# MCU.net
KiCad netlist of a schematic drawn in Altium Designer
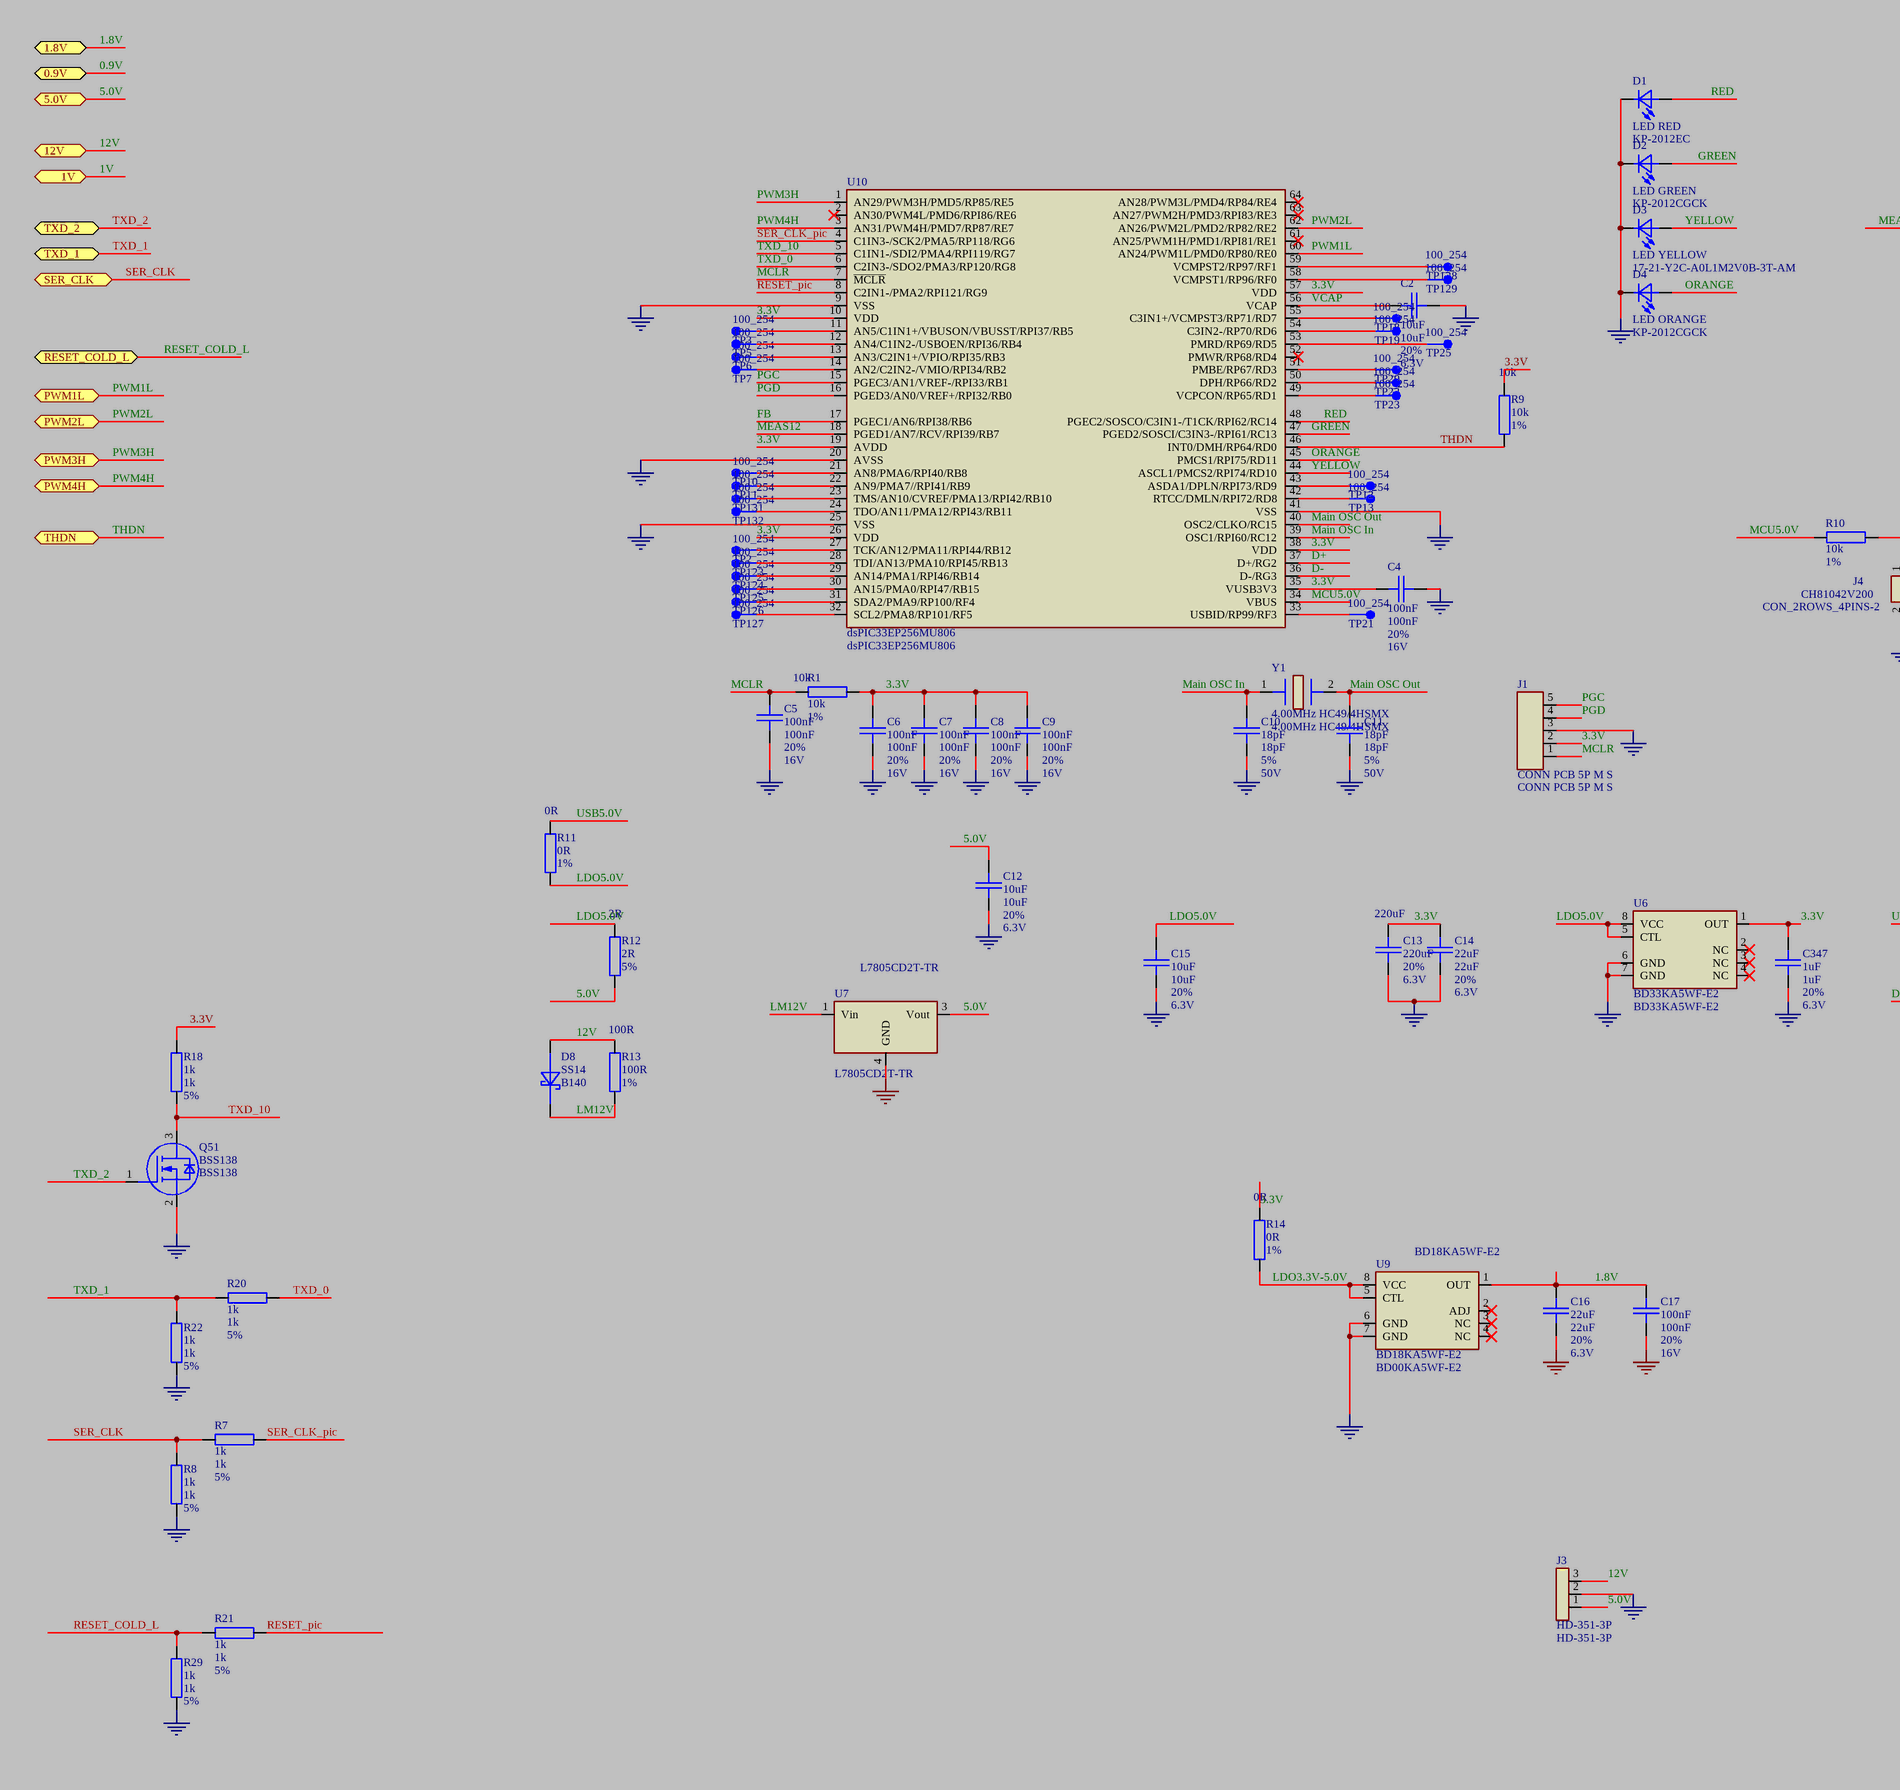
[diagram p0: MCU.SchDoc, left]
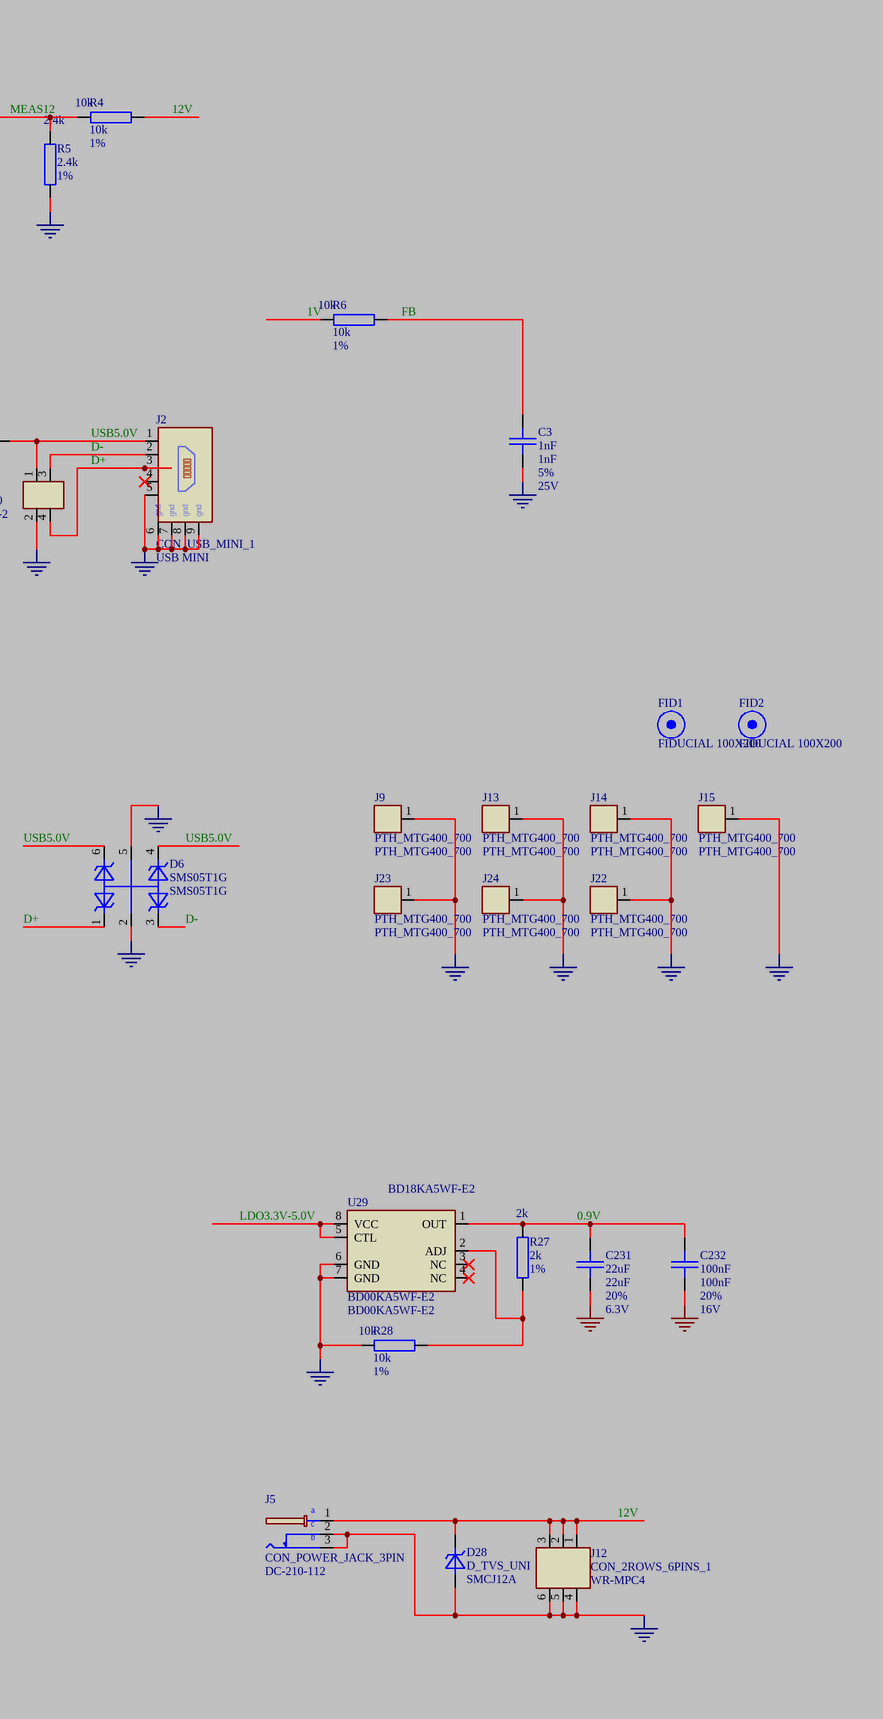
[diagram p1: MCU.SchDoc, right]

(export (version "E")
  (design (tool "Eeschema 10.0.6"))
  (components
    (comp (ref "C2")
      (value "10uF")
      (footprint "SMD_0603_CAPC1608X95N")
      (fields
        (field (name "DB_PART_NUMBER") "CAP000043646")
        (field (name "DB_VALUE") "10uF")
        (field (name "DB_TOLERANCE") "20%")
        (field (name "DB_VOLTAGE") "6.3V")
        (field (name "DB_MANUFACTURER_PART") "KEMET    C0603C106M9PAC")
        (field (name "DB_APPROVED_BY") "ISHIDDEN=T")
      )
      (libsource (lib "Database_Libs1") (part "C"))
    )
    (comp (ref "C3")
      (value "1nF")
      (footprint "SMD_0603_CAPC1608X95N")
      (fields
        (field (name "DB_PART_NUMBER") "CAP000024113")
        (field (name "DB_VALUE") "1nF")
        (field (name "DB_TOLERANCE") "5%")
        (field (name "DB_VOLTAGE") "25V")
        (field (name "DB_MANUFACTURER_PART") "KEMET    C0603C102J3RAC")
        (field (name "DB_APPROVED_BY") "ISHIDDEN=T")
      )
      (libsource (lib "Database_Libs1") (part "C"))
    )
    (comp (ref "C4")
      (value "100nF")
      (footprint "SMD_0402_CAPC1005X55N")
      (fields
        (field (name "DB_PART_NUMBER") "CAP000022751")
        (field (name "DB_VALUE") "100nF")
        (field (name "DB_TOLERANCE") "20%")
        (field (name "DB_VOLTAGE") "16V")
        (field (name "DB_MANUFACTURER_PART") "KEMET    C0402F104M4RAC")
        (field (name "DB_APPROVED_BY") "ISHIDDEN=T")
      )
      (libsource (lib "Database_Libs1") (part "C"))
    )
    (comp (ref "C5")
      (value "100nF")
      (footprint "SMD_0402_CAPC1005X55N")
      (fields
        (field (name "DB_PART_NUMBER") "CAP000022751")
        (field (name "DB_VALUE") "100nF")
        (field (name "DB_TOLERANCE") "20%")
        (field (name "DB_VOLTAGE") "16V")
        (field (name "DB_MANUFACTURER_PART") "KEMET    C0402F104M4RAC")
        (field (name "DB_APPROVED_BY") "ISHIDDEN=T")
      )
      (libsource (lib "Database_Libs1") (part "C"))
    )
    (comp (ref "C6")
      (value "100nF")
      (footprint "SMD_0402_CAPC1005X55N")
      (fields
        (field (name "DB_PART_NUMBER") "CAP000022751")
        (field (name "DB_VALUE") "100nF")
        (field (name "DB_TOLERANCE") "20%")
        (field (name "DB_VOLTAGE") "16V")
        (field (name "DB_MANUFACTURER_PART") "KEMET    C0402F104M4RAC")
        (field (name "DB_APPROVED_BY") "ISHIDDEN=T")
      )
      (libsource (lib "Database_Libs1") (part "C"))
    )
    (comp (ref "C7")
      (value "100nF")
      (footprint "SMD_0402_CAPC1005X55N")
      (fields
        (field (name "DB_PART_NUMBER") "CAP000022751")
        (field (name "DB_VALUE") "100nF")
        (field (name "DB_TOLERANCE") "20%")
        (field (name "DB_VOLTAGE") "16V")
        (field (name "DB_MANUFACTURER_PART") "KEMET    C0402F104M4RAC")
        (field (name "DB_APPROVED_BY") "ISHIDDEN=T")
      )
      (libsource (lib "Database_Libs1") (part "C"))
    )
    (comp (ref "C8")
      (value "100nF")
      (footprint "SMD_0402_CAPC1005X55N")
      (fields
        (field (name "DB_PART_NUMBER") "CAP000022751")
        (field (name "DB_VALUE") "100nF")
        (field (name "DB_TOLERANCE") "20%")
        (field (name "DB_VOLTAGE") "16V")
        (field (name "DB_MANUFACTURER_PART") "KEMET    C0402F104M4RAC")
        (field (name "DB_APPROVED_BY") "ISHIDDEN=T")
      )
      (libsource (lib "Database_Libs1") (part "C"))
    )
    (comp (ref "C9")
      (value "100nF")
      (footprint "SMD_0402_CAPC1005X55N")
      (fields
        (field (name "DB_PART_NUMBER") "CAP000022751")
        (field (name "DB_VALUE") "100nF")
        (field (name "DB_TOLERANCE") "20%")
        (field (name "DB_VOLTAGE") "16V")
        (field (name "DB_MANUFACTURER_PART") "KEMET    C0402F104M4RAC")
        (field (name "DB_APPROVED_BY") "ISHIDDEN=T")
      )
      (libsource (lib "Database_Libs1") (part "C"))
    )
    (comp (ref "C10")
      (value "18pF")
      (footprint "SMD_0603_CAPC1608X95N")
      (fields
        (field (name "DB_PART_NUMBER") "CAP000031922")
        (field (name "DB_VALUE") "18pF")
        (field (name "DB_TOLERANCE") "5%")
        (field (name "DB_VOLTAGE") "50V")
        (field (name "DB_MANUFACTURER_PART") "KEMET    C0603C180J5GAC")
        (field (name "DB_APPROVED_BY") "ISHIDDEN=T")
      )
      (libsource (lib "Database_Libs1") (part "C"))
    )
    (comp (ref "C11")
      (value "18pF")
      (footprint "SMD_0603_CAPC1608X95N")
      (fields
        (field (name "DB_PART_NUMBER") "CAP000031922")
        (field (name "DB_VALUE") "18pF")
        (field (name "DB_TOLERANCE") "5%")
        (field (name "DB_VOLTAGE") "50V")
        (field (name "DB_MANUFACTURER_PART") "KEMET    C0603C180J5GAC")
        (field (name "DB_APPROVED_BY") "ISHIDDEN=T")
      )
      (libsource (lib "Database_Libs1") (part "C"))
    )
    (comp (ref "C12")
      (value "10uF")
      (footprint "SMD_0603_CAPC1608X95N")
      (fields
        (field (name "DB_PART_NUMBER") "CAP000043646")
        (field (name "DB_VALUE") "10uF")
        (field (name "DB_TOLERANCE") "20%")
        (field (name "DB_VOLTAGE") "6.3V")
        (field (name "DB_MANUFACTURER_PART") "KEMET    C0603C106M9PAC")
        (field (name "DB_APPROVED_BY") "ISHIDDEN=T")
      )
      (libsource (lib "Database_Libs1") (part "C"))
    )
    (comp (ref "C13")
      (value "220uF")
      (footprint "SMD_1210_CAPC3225X279N")
      (fields
        (field (name "DB_PART_NUMBER") "CAP000047355")
        (field (name "DB_VALUE") "220uF")
        (field (name "DB_TOLERANCE") "20%")
        (field (name "DB_VOLTAGE") "6.3V")
        (field (name "DB_MANUFACTURER_PART") "SAMSUNG    CL32A227MQVNNNE")
        (field (name "DB_APPROVED_BY") "VSN")
      )
      (libsource (lib "Database_Libs1") (part "C"))
    )
    (comp (ref "C14")
      (value "22uF")
      (footprint "SMD_0805_CAPC2012X145N")
      (fields
        (field (name "DB_PART_NUMBER") "CAP000043686")
        (field (name "DB_VALUE") "22uF")
        (field (name "DB_TOLERANCE") "20%")
        (field (name "DB_VOLTAGE") "6.3V")
        (field (name "DB_MANUFACTURER_PART") "KEMET    C0805C226M9PAC")
        (field (name "DB_APPROVED_BY") "ISHIDDEN=T")
      )
      (libsource (lib "Database_Libs1") (part "C"))
    )
    (comp (ref "C15")
      (value "10uF")
      (footprint "SMD_0603_CAPC1608X95N")
      (fields
        (field (name "DB_PART_NUMBER") "CAP000043646")
        (field (name "DB_VALUE") "10uF")
        (field (name "DB_TOLERANCE") "20%")
        (field (name "DB_VOLTAGE") "6.3V")
        (field (name "DB_MANUFACTURER_PART") "KEMET    C0603C106M9PAC")
        (field (name "DB_APPROVED_BY") "ISHIDDEN=T")
      )
      (libsource (lib "Database_Libs1") (part "C"))
    )
    (comp (ref "C16")
      (value "22uF")
      (footprint "SMD_0805_CAPC2012X145N")
      (fields
        (field (name "DB_PART_NUMBER") "CAP000043686")
        (field (name "DB_VALUE") "22uF")
        (field (name "DB_TOLERANCE") "20%")
        (field (name "DB_VOLTAGE") "6.3V")
        (field (name "DB_MANUFACTURER_PART") "KEMET    C0805C226M9PAC")
        (field (name "DB_APPROVED_BY") "ISHIDDEN=T")
      )
      (libsource (lib "Database_Libs1") (part "C"))
    )
    (comp (ref "C17")
      (value "100nF")
      (footprint "SMD_0402_CAPC1005X55N")
      (fields
        (field (name "DB_PART_NUMBER") "CAP000022751")
        (field (name "DB_VALUE") "100nF")
        (field (name "DB_TOLERANCE") "20%")
        (field (name "DB_VOLTAGE") "16V")
        (field (name "DB_MANUFACTURER_PART") "KEMET    C0402F104M4RAC")
        (field (name "DB_APPROVED_BY") "ISHIDDEN=T")
      )
      (libsource (lib "Database_Libs1") (part "C"))
    )
    (comp (ref "C231")
      (value "22uF")
      (footprint "SMD_0805_CAPC2012X145N")
      (fields
        (field (name "DB_PART_NUMBER") "CAP000043686")
        (field (name "DB_VALUE") "22uF")
        (field (name "DB_TOLERANCE") "20%")
        (field (name "DB_VOLTAGE") "6.3V")
        (field (name "DB_MANUFACTURER_PART") "KEMET    C0805C226M9PAC")
        (field (name "DB_APPROVED_BY") "ISHIDDEN=T")
      )
      (libsource (lib "Database_Libs1") (part "C"))
    )
    (comp (ref "C232")
      (value "100nF")
      (footprint "SMD_0402_CAPC1005X55N")
      (fields
        (field (name "DB_PART_NUMBER") "CAP000022751")
        (field (name "DB_VALUE") "100nF")
        (field (name "DB_TOLERANCE") "20%")
        (field (name "DB_VOLTAGE") "16V")
        (field (name "DB_MANUFACTURER_PART") "KEMET    C0402F104M4RAC")
        (field (name "DB_APPROVED_BY") "ISHIDDEN=T")
      )
      (libsource (lib "Database_Libs1") (part "C"))
    )
    (comp (ref "C347")
      (value "1uF")
      (footprint "SMD_0603_CAPC1608X95N")
      (fields
        (field (name "DB_PART_NUMBER") "CAP000043344")
        (field (name "DB_VALUE") "1uF")
        (field (name "DB_TOLERANCE") "20%")
        (field (name "DB_VOLTAGE") "6.3V")
        (field (name "DB_MANUFACTURER_PART") "KEMET    C0603C105M9PAC")
        (field (name "DB_APPROVED_BY") "ISHIDDEN=T")
      )
      (libsource (lib "Database_Libs1") (part "C"))
    )
    (comp (ref "D1")
      (value "LED RED")
      (footprint "SMD_0805_LED2012X100N")
      (fields
        (field (name "DB_PART_NUMBER") "OPT000000095")
        (field (name "DB_VALUE") "KP-2012EC")
        (field (name "DB_MANUFACTURER_PART") "KINGBRIGHT       KP-2012EC")
        (field (name "DB_APPROVED_BY") "VSN")
      )
      (libsource (lib "Database_Libs1") (part "LED"))
    )
    (comp (ref "D2")
      (value "LED GREEN")
      (footprint "SMD_0805_LED2012X100N")
      (fields
        (field (name "DB_PART_NUMBER") "OPT000000096")
        (field (name "DB_VALUE") "KP-2012CGCK")
        (field (name "DB_MANUFACTURER_PART") "KINGBRIGHT       KP-2012CGCK")
        (field (name "DB_APPROVED_BY") "VSN")
      )
      (libsource (lib "Database_Libs1") (part "LED"))
    )
    (comp (ref "D3")
      (value "LED YELLOW")
      (footprint "SMD_0805_LED2012X100N")
      (fields
        (field (name "DB_PART_NUMBER") "OPT000000092")
        (field (name "DB_VALUE") "17-21-Y2C-A0L1M2V0B-3T-AM")
        (field (name "DB_MANUFACTURER_PART") "EVERLIGHT       17-21-Y2C-A0L1M2V0B-3T-AM")
        (field (name "DB_APPROVED_BY") "VSN")
      )
      (libsource (lib "Database_Libs1") (part "LED"))
    )
    (comp (ref "D4")
      (value "LED ORANGE")
      (footprint "SMD_0805_LED2012X100N")
      (fields
        (field (name "DB_PART_NUMBER") "OPT0000000zz")
        (field (name "DB_VALUE") "KP-2012CGCK")
        (field (name "DB_MANUFACTURER_PART") "KINGBRIGHT       KP-2012CGCK")
        (field (name "DB_APPROVED_BY") "VSN")
      )
      (libsource (lib "Database_Libs1") (part "LED"))
    )
    (comp (ref "D6")
      (value "SMS05T1G")
      (footprint "SMD_SOT457_SOT95P275X110-6N")
      (fields
        (field (name "DB_PART_NUMBER") "DDE000002846")
        (field (name "DB_VALUE") "SMS05T1G")
        (field (name "DB_MANUFACTURER_PART") "ON SEMICONDUCTOR        SMS05T1G")
        (field (name "DB_APPROVED_BY") "VSN")
      )
      (libsource (lib "Database_Libs1") (part "D_TVS_QUAD_C1A2C3C4A5C6"))
    )
    (comp (ref "D8")
      (value "SS14")
      (footprint "SMD_DO214AC_SMA")
      (fields
        (field (name "DB_PART_NUMBER") "DDE000000580")
        (field (name "DB_VALUE") "B140")
        (field (name "DB_MANUFACTURER_PART") "Diodes        B140")
        (field (name "DB_APPROVED_BY") "ISHIDDEN=T")
      )
      (libsource (lib "Database_Libs1") (part "D_STKY"))
    )
    (comp (ref "D28")
      (value "D_TVS_UNI")
      (footprint "SMD_DO214AC_SMC")
      (fields
        (field (name "DB_PART_NUMBER") "DDE000001725")
        (field (name "DB_VALUE") "SMCJ12A")
        (field (name "DB_MANUFACTURER_PART") "Diodes        SMCJ12A")
        (field (name "DB_APPROVED_BY") "ISHIDDEN=T")
      )
      (libsource (lib "Database_Libs1") (part "D_TVS_UNI"))
    )
    (comp (ref "FID1")
      (value "FIDUCIAL 100X200")
      (footprint "FID100X200")
      (fields
        (field (name "DB_PART_NUMBER") "FID000000001")
        (field (name "DB_MANUFACTURER_PART") "ISHIDDEN=T")
        (field (name "DB_APPROVED_BY") "ISHIDDEN=T")
      )
      (libsource (lib "Database_Libs1") (part "FIDUCIAL"))
    )
    (comp (ref "FID2")
      (value "FIDUCIAL 100X200")
      (footprint "FID100X200")
      (fields
        (field (name "DB_PART_NUMBER") "FID000000001")
        (field (name "DB_MANUFACTURER_PART") "ISHIDDEN=T")
        (field (name "DB_APPROVED_BY") "ISHIDDEN=T")
      )
      (libsource (lib "Database_Libs1") (part "FIDUCIAL"))
    )
    (comp (ref "J1")
      (value "CONN PCB 5P M S")
      (footprint "PTH_HDRV05W64P254_1X05")
      (fields
        (field (name "DB_PART_NUMBER") "CON000000006")
        (field (name "DB_VALUE") "CONN PCB 5P M S")
        (field (name "DB_MANUFACTURER_PART") "W+P        143-12-005-00")
        (field (name "DB_APPROVED_BY") "VSN")
      )
      (libsource (lib "Database_Libs1") (part "CON_5PINS"))
    )
    (comp (ref "J2")
      (value "CON_USB_MINI_1")
      (footprint "SMD_CON-CVILUX-CU04-SCM15B0")
      (fields
        (field (name "DB_PART_NUMBER") "CON000000048")
        (field (name "DB_VALUE") "USB MINI")
        (field (name "DB_MANUFACTURER_PART") "CVILUX       CU04-SCM15B0-R0-LF")
        (field (name "DB_APPROVED_BY") "VSN")
      )
      (libsource (lib "Database_Libs1") (part "CON_USB_MINI_1"))
    )
    (comp (ref "J3")
      (value "HD-351-3P")
      (footprint "PTH_CON_HD-351-3P")
      (fields
        (field (name "DB_PART_NUMBER") "CON000000272")
        (field (name "DB_VALUE") "HD-351-3P")
        (field (name "DB_MANUFACTURER_PART") "HOW DER      HD-351-3P")
        (field (name "DB_APPROVED_BY") "VSN")
      )
      (libsource (lib "Database_Libs1") (part "CON_3PINS"))
    )
    (comp (ref "J4")
      (value "CON_2ROWS_4PINS-2")
      (footprint "PTH_HDRV40W6240P254_2X02_M")
      (fields
        (field (name "DB_PART_NUMBER") "CON000000298")
        (field (name "DB_VALUE") "CH81042V200")
        (field (name "DB_MANUFACTURER_PART") "CVILUX        CH81042V200")
        (field (name "DB_APPROVED_BY") "VSN")
      )
      (libsource (lib "Database_Libs1") (part "CON_2ROWS_4PINS-2"))
    )
    (comp (ref "J5")
      (value "CON_POWER_JACK_3PIN")
      (footprint "PTH_DC-POWER-JACK_210-112")
      (fields
        (field (name "DB_PART_NUMBER") "CON000000026")
        (field (name "DB_VALUE") "DC-210-112")
        (field (name "DB_MANUFACTURER_PART") "HONBO       DC-210-112")
        (field (name "DB_APPROVED_BY") "VSN")
      )
      (libsource (lib "Database_Libs1") (part "CON_POWER_JACK_3PIN"))
    )
    (comp (ref "J9")
      (value "PTH_MTG400_700")
      (footprint "PTH_MTG400_700")
      (fields
        (field (name "DB_PART_NUMBER") "MTH000000030")
        (field (name "DB_VALUE") "PTH_MTG400_700")
        (field (name "DB_APPROVED_BY") "VSN")
      )
      (libsource (lib "Database_Libs1") (part "CON_1PIN"))
    )
    (comp (ref "J12")
      (value "CON_2ROWS_6PINS_1")
      (footprint "PTH_CON_WR-MRC4-6P_S")
      (fields
        (field (name "DB_PART_NUMBER") "CON000000279")
        (field (name "DB_VALUE") "WR-MPC4")
        (field (name "DB_MANUFACTURER_PART") "WE        	649 006 211 22")
        (field (name "DB_APPROVED_BY") "VSN")
      )
      (libsource (lib "Database_Libs1") (part "CON_2ROWS_6PINS_1"))
    )
    (comp (ref "J13")
      (value "PTH_MTG400_700")
      (footprint "PTH_MTG400_700")
      (fields
        (field (name "DB_PART_NUMBER") "MTH000000030")
        (field (name "DB_VALUE") "PTH_MTG400_700")
        (field (name "DB_APPROVED_BY") "VSN")
      )
      (libsource (lib "Database_Libs1") (part "CON_1PIN"))
    )
    (comp (ref "J14")
      (value "PTH_MTG400_700")
      (footprint "PTH_MTG400_700")
      (fields
        (field (name "DB_PART_NUMBER") "MTH000000030")
        (field (name "DB_VALUE") "PTH_MTG400_700")
        (field (name "DB_APPROVED_BY") "VSN")
      )
      (libsource (lib "Database_Libs1") (part "CON_1PIN"))
    )
    (comp (ref "J15")
      (value "PTH_MTG400_700")
      (footprint "PTH_MTG400_700")
      (fields
        (field (name "DB_PART_NUMBER") "MTH000000030")
        (field (name "DB_VALUE") "PTH_MTG400_700")
        (field (name "DB_APPROVED_BY") "VSN")
      )
      (libsource (lib "Database_Libs1") (part "CON_1PIN"))
    )
    (comp (ref "J22")
      (value "PTH_MTG400_700")
      (footprint "PTH_MTG400_700")
      (fields
        (field (name "DB_PART_NUMBER") "MTH000000030")
        (field (name "DB_VALUE") "PTH_MTG400_700")
        (field (name "DB_APPROVED_BY") "VSN")
      )
      (libsource (lib "Database_Libs1") (part "CON_1PIN"))
    )
    (comp (ref "J23")
      (value "PTH_MTG400_700")
      (footprint "PTH_MTG400_700")
      (fields
        (field (name "DB_PART_NUMBER") "MTH000000030")
        (field (name "DB_VALUE") "PTH_MTG400_700")
        (field (name "DB_APPROVED_BY") "VSN")
      )
      (libsource (lib "Database_Libs1") (part "CON_1PIN"))
    )
    (comp (ref "J24")
      (value "PTH_MTG400_700")
      (footprint "PTH_MTG400_700")
      (fields
        (field (name "DB_PART_NUMBER") "MTH000000030")
        (field (name "DB_VALUE") "PTH_MTG400_700")
        (field (name "DB_APPROVED_BY") "VSN")
      )
      (libsource (lib "Database_Libs1") (part "CON_1PIN"))
    )
    (comp (ref "Q51")
      (value "BSS138")
      (footprint "SMD_SOT23_SOT95P240X112-3N")
      (fields
        (field (name "DB_PART_NUMBER") "TRA000001460")
        (field (name "DB_VALUE") "BSS138")
        (field (name "DB_MANUFACTURER_PART") "FAIRCHILD        BSS138LT1G")
        (field (name "DB_APPROVED_BY") "VSN")
      )
      (libsource (lib "Database_Libs1") (part "MOS_N_D1_G1S2D3"))
    )
    (comp (ref "R1")
      (value "10k")
      (footprint "SMD_0603_RESC1608X55N")
      (fields
        (field (name "DB_PART_NUMBER") "RES000008663")
        (field (name "DB_VALUE") "10k")
        (field (name "DB_TOLERANCE") "1%")
        (field (name "DB_MANUFACTURER_PART") "YAGEO    RC0603FR-0710KL")
        (field (name "DB_APPROVED_BY") "VSN")
      )
      (libsource (lib "Database_Libs1") (part "R"))
    )
    (comp (ref "R4")
      (value "10k")
      (footprint "SMD_0603_RESC1608X55N")
      (fields
        (field (name "DB_PART_NUMBER") "RES000008663")
        (field (name "DB_VALUE") "10k")
        (field (name "DB_TOLERANCE") "1%")
        (field (name "DB_MANUFACTURER_PART") "YAGEO    RC0603FR-0710KL")
        (field (name "DB_APPROVED_BY") "VSN")
      )
      (libsource (lib "Database_Libs1") (part "R"))
    )
    (comp (ref "R5")
      (value "2.4k")
      (footprint "SMD_0603_RESC1608X55N")
      (fields
        (field (name "DB_PART_NUMBER") "RES000006261")
        (field (name "DB_VALUE") "2.4k")
        (field (name "DB_TOLERANCE") "1%")
        (field (name "DB_MANUFACTURER_PART") "YAGEO    RC0603FR-072K4")
        (field (name "DB_APPROVED_BY") "ISHIDDEN=T")
      )
      (libsource (lib "Database_Libs1") (part "R"))
    )
    (comp (ref "R6")
      (value "10k")
      (footprint "SMD_0603_RESC1608X55N")
      (fields
        (field (name "DB_PART_NUMBER") "RES000008663")
        (field (name "DB_VALUE") "10k")
        (field (name "DB_TOLERANCE") "1%")
        (field (name "DB_MANUFACTURER_PART") "YAGEO    RC0603FR-0710KL")
        (field (name "DB_APPROVED_BY") "VSN")
      )
      (libsource (lib "Database_Libs1") (part "R"))
    )
    (comp (ref "R7")
      (value "1k")
      (footprint "SMD_0603_RESC1608X55N")
      (fields
        (field (name "DB_PART_NUMBER") "RES000008858")
        (field (name "DB_VALUE") "1k")
        (field (name "DB_TOLERANCE") "5%")
        (field (name "DB_MANUFACTURER_PART") "YAGEO    AC0603JR-071KL")
        (field (name "DB_APPROVED_BY") "VSN")
      )
      (libsource (lib "Database_Libs1") (part "R"))
    )
    (comp (ref "R8")
      (value "1k")
      (footprint "SMD_0603_RESC1608X55N")
      (fields
        (field (name "DB_PART_NUMBER") "RES000008858")
        (field (name "DB_VALUE") "1k")
        (field (name "DB_TOLERANCE") "5%")
        (field (name "DB_MANUFACTURER_PART") "YAGEO    AC0603JR-071KL")
        (field (name "DB_APPROVED_BY") "VSN")
      )
      (libsource (lib "Database_Libs1") (part "R"))
    )
    (comp (ref "R9")
      (value "10k")
      (footprint "SMD_0603_RESC1608X55N")
      (fields
        (field (name "DB_PART_NUMBER") "RES000008663")
        (field (name "DB_VALUE") "10k")
        (field (name "DB_TOLERANCE") "1%")
        (field (name "DB_MANUFACTURER_PART") "YAGEO    RC0603FR-0710KL")
        (field (name "DB_APPROVED_BY") "VSN")
      )
      (libsource (lib "Database_Libs1") (part "R"))
    )
    (comp (ref "R10")
      (value "R")
      (footprint "SMD_0603_RESC1608X55N")
      (fields
        (field (name "DB_PART_NUMBER") "RES000008663")
        (field (name "DB_VALUE") "10k")
        (field (name "DB_TOLERANCE") "1%")
        (field (name "DB_MANUFACTURER_PART") "YAGEO    RC0603FR-0710KL")
        (field (name "DB_APPROVED_BY") "VSN")
      )
      (libsource (lib "Database_Libs1") (part "R"))
    )
    (comp (ref "R11")
      (value "0R")
      (footprint "SMD_0603_RESC1608X55N")
      (fields
        (field (name "DB_PART_NUMBER") "RES000008926")
        (field (name "DB_VALUE") "0R")
        (field (name "DB_TOLERANCE") "1%")
        (field (name "DB_MANUFACTURER_PART") "YAGEO    AC0603FR-070RL")
        (field (name "DB_APPROVED_BY") "VSN")
      )
      (libsource (lib "Database_Libs1") (part "R"))
    )
    (comp (ref "R12")
      (value "2R")
      (footprint "SMD_1206_RESC3216X65N")
      (fields
        (field (name "DB_PART_NUMBER") "RES000007051")
        (field (name "DB_VALUE") "2R")
        (field (name "DB_TOLERANCE") "5%")
        (field (name "DB_MANUFACTURER_PART") "YAGEO    RC1206JR-072R")
        (field (name "DB_APPROVED_BY") "ISHIDDEN=T")
      )
      (libsource (lib "Database_Libs1") (part "R"))
    )
    (comp (ref "R13")
      (value "100R")
      (footprint "SMD_1206_RESC3216X65N")
      (fields
        (field (name "DB_PART_NUMBER") "RES000006922")
        (field (name "DB_VALUE") "100R")
        (field (name "DB_TOLERANCE") "1%")
        (field (name "DB_MANUFACTURER_PART") "YAGEO    RC1206FR-07100R")
        (field (name "DB_APPROVED_BY") "ISHIDDEN=T")
      )
      (libsource (lib "Database_Libs1") (part "R"))
    )
    (comp (ref "R14")
      (value "0R")
      (footprint "SMD_1206_RESC3216X65N")
      (fields
        (field (name "DB_PART_NUMBER") "RES000008756")
        (field (name "DB_VALUE") "0R")
        (field (name "DB_TOLERANCE") "1%")
        (field (name "DB_MANUFACTURER_PART") "YAGEO    AC1206FR-070RL")
        (field (name "DB_APPROVED_BY") "VSN")
      )
      (libsource (lib "Database_Libs1") (part "R"))
    )
    (comp (ref "R18")
      (value "1k")
      (footprint "SMD_0603_RESC1608X55N")
      (fields
        (field (name "DB_PART_NUMBER") "RES000008858")
        (field (name "DB_VALUE") "1k")
        (field (name "DB_TOLERANCE") "5%")
        (field (name "DB_MANUFACTURER_PART") "YAGEO    AC0603JR-071KL")
        (field (name "DB_APPROVED_BY") "VSN")
      )
      (libsource (lib "Database_Libs1") (part "R"))
    )
    (comp (ref "R20")
      (value "1k")
      (footprint "SMD_0603_RESC1608X55N")
      (fields
        (field (name "DB_PART_NUMBER") "RES000008858")
        (field (name "DB_VALUE") "1k")
        (field (name "DB_TOLERANCE") "5%")
        (field (name "DB_MANUFACTURER_PART") "YAGEO    AC0603JR-071KL")
        (field (name "DB_APPROVED_BY") "VSN")
      )
      (libsource (lib "Database_Libs1") (part "R"))
    )
    (comp (ref "R21")
      (value "1k")
      (footprint "SMD_0603_RESC1608X55N")
      (fields
        (field (name "DB_PART_NUMBER") "RES000008858")
        (field (name "DB_VALUE") "1k")
        (field (name "DB_TOLERANCE") "5%")
        (field (name "DB_MANUFACTURER_PART") "YAGEO    AC0603JR-071KL")
        (field (name "DB_APPROVED_BY") "VSN")
      )
      (libsource (lib "Database_Libs1") (part "R"))
    )
    (comp (ref "R22")
      (value "1k")
      (footprint "SMD_0603_RESC1608X55N")
      (fields
        (field (name "DB_PART_NUMBER") "RES000008858")
        (field (name "DB_VALUE") "1k")
        (field (name "DB_TOLERANCE") "5%")
        (field (name "DB_MANUFACTURER_PART") "YAGEO    AC0603JR-071KL")
        (field (name "DB_APPROVED_BY") "VSN")
      )
      (libsource (lib "Database_Libs1") (part "R"))
    )
    (comp (ref "R27")
      (value "2k")
      (footprint "SMD_0603_RESC1608X55N")
      (fields
        (field (name "DB_PART_NUMBER") "RES000006259")
        (field (name "DB_VALUE") "2k")
        (field (name "DB_TOLERANCE") "1%")
        (field (name "DB_MANUFACTURER_PART") "YAGEO    RC0603FR-072K")
        (field (name "DB_APPROVED_BY") "ISHIDDEN=T")
      )
      (libsource (lib "Database_Libs1") (part "R"))
    )
    (comp (ref "R28")
      (value "10k")
      (footprint "SMD_0603_RESC1608X55N")
      (fields
        (field (name "DB_PART_NUMBER") "RES000006276")
        (field (name "DB_VALUE") "10k")
        (field (name "DB_TOLERANCE") "1%")
        (field (name "DB_MANUFACTURER_PART") "YAGEO    RC0603FR-0710K")
        (field (name "DB_APPROVED_BY") "ISHIDDEN=T")
      )
      (libsource (lib "Database_Libs1") (part "R"))
    )
    (comp (ref "R29")
      (value "1k")
      (footprint "SMD_0603_RESC1608X55N")
      (fields
        (field (name "DB_PART_NUMBER") "RES000008858")
        (field (name "DB_VALUE") "1k")
        (field (name "DB_TOLERANCE") "5%")
        (field (name "DB_MANUFACTURER_PART") "YAGEO    AC0603JR-071KL")
        (field (name "DB_APPROVED_BY") "VSN")
      )
      (libsource (lib "Database_Libs1") (part "R"))
    )
    (comp (ref "TP2")
      (value "100_254")
      (footprint "SMD_TP_100-254")
      (fields
        (field (name "DB_PART_NUMBER") "TPO000000001")
        (field (name "DB_MANUFACTURER_PART") "ISHIDDEN=T")
        (field (name "DB_APPROVED_BY") "ISHIDDEN=T")
      )
      (libsource (lib "Database_Libs1") (part "TEST_POINT_1"))
    )
    (comp (ref "TP3")
      (value "100_254")
      (footprint "SMD_TP_100-254")
      (fields
        (field (name "DB_PART_NUMBER") "TPO000000001")
        (field (name "DB_MANUFACTURER_PART") "ISHIDDEN=T")
        (field (name "DB_APPROVED_BY") "ISHIDDEN=T")
      )
      (libsource (lib "Database_Libs1") (part "TEST_POINT_1"))
    )
    (comp (ref "TP5")
      (value "100_254")
      (footprint "SMD_TP_100-254")
      (fields
        (field (name "DB_PART_NUMBER") "TPO000000001")
        (field (name "DB_MANUFACTURER_PART") "ISHIDDEN=T")
        (field (name "DB_APPROVED_BY") "ISHIDDEN=T")
      )
      (libsource (lib "Database_Libs1") (part "TEST_POINT_1"))
    )
    (comp (ref "TP6")
      (value "100_254")
      (footprint "SMD_TP_100-254")
      (fields
        (field (name "DB_PART_NUMBER") "TPO000000001")
        (field (name "DB_MANUFACTURER_PART") "ISHIDDEN=T")
        (field (name "DB_APPROVED_BY") "ISHIDDEN=T")
      )
      (libsource (lib "Database_Libs1") (part "TEST_POINT_1"))
    )
    (comp (ref "TP7")
      (value "100_254")
      (footprint "SMD_TP_100-254")
      (fields
        (field (name "DB_PART_NUMBER") "TPO000000001")
        (field (name "DB_MANUFACTURER_PART") "ISHIDDEN=T")
        (field (name "DB_APPROVED_BY") "ISHIDDEN=T")
      )
      (libsource (lib "Database_Libs1") (part "TEST_POINT_1"))
    )
    (comp (ref "TP10")
      (value "100_254")
      (footprint "SMD_TP_100-254")
      (fields
        (field (name "DB_PART_NUMBER") "TPO000000001")
        (field (name "DB_MANUFACTURER_PART") "ISHIDDEN=T")
        (field (name "DB_APPROVED_BY") "ISHIDDEN=T")
      )
      (libsource (lib "Database_Libs1") (part "TEST_POINT_1"))
    )
    (comp (ref "TP11")
      (value "100_254")
      (footprint "SMD_TP_100-254")
      (fields
        (field (name "DB_PART_NUMBER") "TPO000000001")
        (field (name "DB_MANUFACTURER_PART") "ISHIDDEN=T")
        (field (name "DB_APPROVED_BY") "ISHIDDEN=T")
      )
      (libsource (lib "Database_Libs1") (part "TEST_POINT_1"))
    )
    (comp (ref "TP12")
      (value "100_254")
      (footprint "SMD_TP_100-254")
      (fields
        (field (name "DB_PART_NUMBER") "TPO000000001")
        (field (name "DB_MANUFACTURER_PART") "ISHIDDEN=T")
        (field (name "DB_APPROVED_BY") "ISHIDDEN=T")
      )
      (libsource (lib "Database_Libs1") (part "TEST_POINT_1"))
    )
    (comp (ref "TP13")
      (value "100_254")
      (footprint "SMD_TP_100-254")
      (fields
        (field (name "DB_PART_NUMBER") "TPO000000001")
        (field (name "DB_MANUFACTURER_PART") "ISHIDDEN=T")
        (field (name "DB_APPROVED_BY") "ISHIDDEN=T")
      )
      (libsource (lib "Database_Libs1") (part "TEST_POINT_1"))
    )
    (comp (ref "TP18")
      (value "100_254")
      (footprint "SMD_TP_100-254")
      (fields
        (field (name "DB_PART_NUMBER") "TPO000000001")
        (field (name "DB_MANUFACTURER_PART") "ISHIDDEN=T")
        (field (name "DB_APPROVED_BY") "ISHIDDEN=T")
      )
      (libsource (lib "Database_Libs1") (part "TEST_POINT_1"))
    )
    (comp (ref "TP19")
      (value "100_254")
      (footprint "SMD_TP_100-254")
      (fields
        (field (name "DB_PART_NUMBER") "TPO000000001")
        (field (name "DB_MANUFACTURER_PART") "ISHIDDEN=T")
        (field (name "DB_APPROVED_BY") "ISHIDDEN=T")
      )
      (libsource (lib "Database_Libs1") (part "TEST_POINT_1"))
    )
    (comp (ref "TP20")
      (value "100_254")
      (footprint "SMD_TP_100-254")
      (fields
        (field (name "DB_PART_NUMBER") "TPO000000001")
        (field (name "DB_MANUFACTURER_PART") "ISHIDDEN=T")
        (field (name "DB_APPROVED_BY") "ISHIDDEN=T")
      )
      (libsource (lib "Database_Libs1") (part "TEST_POINT_1"))
    )
    (comp (ref "TP21")
      (value "100_254")
      (footprint "SMD_TP_100-254")
      (fields
        (field (name "DB_PART_NUMBER") "TPO000000001")
        (field (name "DB_MANUFACTURER_PART") "ISHIDDEN=T")
        (field (name "DB_APPROVED_BY") "ISHIDDEN=T")
      )
      (libsource (lib "Database_Libs1") (part "TEST_POINT_1"))
    )
    (comp (ref "TP22")
      (value "100_254")
      (footprint "SMD_TP_100-254")
      (fields
        (field (name "DB_PART_NUMBER") "TPO000000001")
        (field (name "DB_MANUFACTURER_PART") "ISHIDDEN=T")
        (field (name "DB_APPROVED_BY") "ISHIDDEN=T")
      )
      (libsource (lib "Database_Libs1") (part "TEST_POINT_1"))
    )
    (comp (ref "TP23")
      (value "100_254")
      (footprint "SMD_TP_100-254")
      (fields
        (field (name "DB_PART_NUMBER") "TPO000000001")
        (field (name "DB_MANUFACTURER_PART") "ISHIDDEN=T")
        (field (name "DB_APPROVED_BY") "ISHIDDEN=T")
      )
      (libsource (lib "Database_Libs1") (part "TEST_POINT_1"))
    )
    (comp (ref "TP25")
      (value "100_254")
      (footprint "SMD_TP_100-254")
      (fields
        (field (name "DB_PART_NUMBER") "TPO000000001")
        (field (name "DB_MANUFACTURER_PART") "ISHIDDEN=T")
        (field (name "DB_APPROVED_BY") "ISHIDDEN=T")
      )
      (libsource (lib "Database_Libs1") (part "TEST_POINT_1"))
    )
    (comp (ref "TP123")
      (value "100_254")
      (footprint "SMD_TP_100-254")
      (fields
        (field (name "DB_PART_NUMBER") "TPO000000001")
        (field (name "DB_MANUFACTURER_PART") "ISHIDDEN=T")
        (field (name "DB_APPROVED_BY") "ISHIDDEN=T")
      )
      (libsource (lib "Database_Libs1") (part "TEST_POINT_1"))
    )
    (comp (ref "TP124")
      (value "100_254")
      (footprint "SMD_TP_100-254")
      (fields
        (field (name "DB_PART_NUMBER") "TPO000000001")
        (field (name "DB_MANUFACTURER_PART") "ISHIDDEN=T")
        (field (name "DB_APPROVED_BY") "ISHIDDEN=T")
      )
      (libsource (lib "Database_Libs1") (part "TEST_POINT_1"))
    )
    (comp (ref "TP125")
      (value "100_254")
      (footprint "SMD_TP_100-254")
      (fields
        (field (name "DB_PART_NUMBER") "TPO000000001")
        (field (name "DB_MANUFACTURER_PART") "ISHIDDEN=T")
        (field (name "DB_APPROVED_BY") "ISHIDDEN=T")
      )
      (libsource (lib "Database_Libs1") (part "TEST_POINT_1"))
    )
    (comp (ref "TP126")
      (value "100_254")
      (footprint "SMD_TP_100-254")
      (fields
        (field (name "DB_PART_NUMBER") "TPO000000001")
        (field (name "DB_MANUFACTURER_PART") "ISHIDDEN=T")
        (field (name "DB_APPROVED_BY") "ISHIDDEN=T")
      )
      (libsource (lib "Database_Libs1") (part "TEST_POINT_1"))
    )
    (comp (ref "TP127")
      (value "100_254")
      (footprint "SMD_TP_100-254")
      (fields
        (field (name "DB_PART_NUMBER") "TPO000000001")
        (field (name "DB_MANUFACTURER_PART") "ISHIDDEN=T")
        (field (name "DB_APPROVED_BY") "ISHIDDEN=T")
      )
      (libsource (lib "Database_Libs1") (part "TEST_POINT_1"))
    )
    (comp (ref "TP128")
      (value "100_254")
      (footprint "SMD_TP_100-254")
      (fields
        (field (name "DB_PART_NUMBER") "TPO000000001")
        (field (name "DB_MANUFACTURER_PART") "ISHIDDEN=T")
        (field (name "DB_APPROVED_BY") "ISHIDDEN=T")
      )
      (libsource (lib "Database_Libs1") (part "TEST_POINT_1"))
    )
    (comp (ref "TP129")
      (value "100_254")
      (footprint "SMD_TP_100-254")
      (fields
        (field (name "DB_PART_NUMBER") "TPO000000001")
        (field (name "DB_MANUFACTURER_PART") "ISHIDDEN=T")
        (field (name "DB_APPROVED_BY") "ISHIDDEN=T")
      )
      (libsource (lib "Database_Libs1") (part "TEST_POINT_1"))
    )
    (comp (ref "TP131")
      (value "100_254")
      (footprint "SMD_TP_100-254")
      (fields
        (field (name "DB_PART_NUMBER") "TPO000000001")
        (field (name "DB_MANUFACTURER_PART") "ISHIDDEN=T")
        (field (name "DB_APPROVED_BY") "ISHIDDEN=T")
      )
      (libsource (lib "Database_Libs1") (part "TEST_POINT_1"))
    )
    (comp (ref "TP132")
      (value "100_254")
      (footprint "SMD_TP_100-254")
      (fields
        (field (name "DB_PART_NUMBER") "TPO000000001")
        (field (name "DB_MANUFACTURER_PART") "ISHIDDEN=T")
        (field (name "DB_APPROVED_BY") "ISHIDDEN=T")
      )
      (libsource (lib "Database_Libs1") (part "TEST_POINT_1"))
    )
    (comp (ref "U6")
      (value "BD33KA5WF-E2")
      (footprint "SMD_SOIC127P620X160-8N")
      (fields
        (field (name "DB_PART_NUMBER") "PSU000000127")
        (field (name "DB_VALUE") "BD33KA5WF-E2")
        (field (name "DB_MANUFACTURER_PART") "ROHM        BD33KA5WF-E2")
        (field (name "DB_APPROVED_BY") "VSN")
      )
      (libsource (lib "Database_Libs1") (part "IC_BDXXKA5WF"))
    )
    (comp (ref "U7")
      (value "L7805CD2T-TR")
      (footprint "SMD_TO254P1542X460-3_4N")
      (fields
        (field (name "DB_PART_NUMBER") "PSU000000129")
        (field (name "DB_VALUE") "L7805CD2T-TR")
        (field (name "DB_MANUFACTURER_PART") "ST       L7805CD2T-TR")
        (field (name "DB_APPROVED_BY") "VSN")
      )
      (libsource (lib "Database_Libs1") (part "IC_IN1OUT3GND4"))
    )
    (comp (ref "U9")
      (value "BD18KA5WF-E2")
      (footprint "SMD_SOIC127P620X160-8N")
      (fields
        (field (name "DB_PART_NUMBER") "PSU000000128")
        (field (name "DB_VALUE") "BD00KA5WF-E2")
        (field (name "DB_MANUFACTURER_PART") "ROHM        BD00KA5WF-E2")
        (field (name "DB_APPROVED_BY") "VSN")
      )
      (libsource (lib "Database_Libs1") (part "IC_BD00KA5WF"))
    )
    (comp (ref "U10")
      (value "dsPIC33EP256MU806")
      (footprint "SMD_QFP50P1200X1200X120-64N")
      (fields
        (field (name "DB_PART_NUMBER") "MCU000000070")
        (field (name "DB_VALUE") "dsPIC33EP256MU806")
        (field (name "DB_MANUFACTURER_PART") "MICROCHIP        DSPIC33EP256MU806-E/PT")
        (field (name "DB_APPROVED_BY") "VSN")
      )
      (libsource (lib "Database_Libs1") (part "IC_DSPIC33EP256MU806-QFN64"))
    )
    (comp (ref "U29")
      (value "BD00KA5WF-E2")
      (footprint "SMD_SOIC127P620X160-8N")
      (fields
        (field (name "DB_PART_NUMBER") "PSU000000128")
        (field (name "DB_VALUE") "BD00KA5WF-E2")
        (field (name "DB_MANUFACTURER_PART") "ROHM        BD00KA5WF-E2")
        (field (name "DB_APPROVED_BY") "VSN")
      )
      (libsource (lib "Database_Libs1") (part "IC_BD00KA5WF"))
    )
    (comp (ref "Y1")
      (value "4.00MHz HC49/4HSMX")
      (footprint "SMD_HC49_XTAL1140X480X420N")
      (fields
        (field (name "DB_PART_NUMBER") "OSC000000012")
        (field (name "DB_VALUE") "4.00MHz HC49/4HSMX")
        (field (name "DB_MANUFACTURER_PART") "IQD       4.00MHz HC49/4HSMX")
        (field (name "DB_APPROVED_BY") "VSN")
      )
      (libsource (lib "Database_Libs1") (part "XTAL"))
    )
  )
  (nets
    (net (code "1") (name "/0.9V") (class "Default")
      (node (ref "C231") (pin "1") (pinfunction "1_1") (pintype "passive"))
      (node (ref "C232") (pin "1") (pinfunction "1_1") (pintype "passive"))
      (node (ref "R27") (pin "1") (pinfunction "1_1") (pintype "passive"))
      (node (ref "U29") (pin "1") (pinfunction "OUT_1") (pintype "passive"))
    )
    (net (code "2") (name "/1.8V") (class "Default")
      (node (ref "C16") (pin "1") (pinfunction "1_1") (pintype "passive"))
      (node (ref "C17") (pin "1") (pinfunction "1_1") (pintype "passive"))
      (node (ref "U9") (pin "1") (pinfunction "OUT_1") (pintype "passive"))
    )
    (net (code "3") (name "/1V") (class "Default")
      (node (ref "R6") (pin "2") (pinfunction "2_2") (pintype "passive"))
    )
    (net (code "4") (name "/3.3V") (class "Default")
      (node (ref "C13") (pin "2") (pinfunction "2_2") (pintype "passive"))
      (node (ref "C14") (pin "1") (pinfunction "1_1") (pintype "passive"))
      (node (ref "C347") (pin "1") (pinfunction "1_1") (pintype "passive"))
      (node (ref "C4") (pin "1") (pinfunction "1_1") (pintype "passive"))
      (node (ref "C6") (pin "1") (pinfunction "1_1") (pintype "passive"))
      (node (ref "C7") (pin "1") (pinfunction "1_1") (pintype "passive"))
      (node (ref "C8") (pin "1") (pinfunction "1_1") (pintype "passive"))
      (node (ref "C9") (pin "1") (pinfunction "1_1") (pintype "passive"))
      (node (ref "J1") (pin "2") (pinfunction "2_2") (pintype "passive"))
      (node (ref "R1") (pin "2") (pinfunction "2_2") (pintype "passive"))
      (node (ref "R14") (pin "2") (pinfunction "2_2") (pintype "passive"))
      (node (ref "R18") (pin "1") (pinfunction "1_1") (pintype "passive"))
      (node (ref "R9") (pin "2") (pinfunction "2_2") (pintype "passive"))
      (node (ref "U10") (pin "10") (pinfunction "VDD_10") (pintype "passive"))
      (node (ref "U10") (pin "19") (pinfunction "AVDD_19") (pintype "passive"))
      (node (ref "U10") (pin "26") (pinfunction "VDD_26") (pintype "passive"))
      (node (ref "U10") (pin "35") (pinfunction "VUSB3V3_35") (pintype "passive"))
      (node (ref "U10") (pin "38") (pinfunction "VDD_38") (pintype "passive"))
      (node (ref "U10") (pin "57") (pinfunction "VDD_57") (pintype "passive"))
      (node (ref "U6") (pin "1") (pinfunction "OUT_1") (pintype "passive"))
    )
    (net (code "5") (name "/5.0V") (class "Default")
      (node (ref "C12") (pin "1") (pinfunction "1_1") (pintype "passive"))
      (node (ref "J3") (pin "1") (pinfunction "1_1") (pintype "passive"))
      (node (ref "R12") (pin "1") (pinfunction "1_1") (pintype "passive"))
      (node (ref "U7") (pin "3") (pinfunction "Vout_3") (pintype "passive"))
    )
    (net (code "6") (name "/12V") (class "Default")
      (node (ref "D28") (pin "1") (pinfunction "C_1") (pintype "passive"))
      (node (ref "D8") (pin "2") (pinfunction "A_2") (pintype "passive"))
      (node (ref "J12") (pin "1") (pinfunction "1_1") (pintype "passive"))
      (node (ref "J12") (pin "2") (pinfunction "2_2") (pintype "passive"))
      (node (ref "J12") (pin "3") (pinfunction "3_3") (pintype "passive"))
      (node (ref "J3") (pin "3") (pinfunction "3_3") (pintype "passive"))
      (node (ref "J5") (pin "1") (pinfunction "1_1") (pintype "passive"))
      (node (ref "R13") (pin "2") (pinfunction "2_2") (pintype "passive"))
      (node (ref "R4") (pin "1") (pinfunction "1_1") (pintype "passive"))
    )
    (net (code "7") (name "/D+") (class "Default")
      (node (ref "D6") (pin "1") (pinfunction "1_1") (pintype "passive"))
      (node (ref "J2") (pin "3") (pinfunction "3_3") (pintype "passive"))
      (node (ref "J4") (pin "4") (pinfunction "4_4") (pintype "passive"))
      (node (ref "U10") (pin "37") (pinfunction "D+/RG2_37") (pintype "passive"))
    )
    (net (code "8") (name "/D-") (class "Default")
      (node (ref "D6") (pin "3") (pinfunction "3_3") (pintype "passive"))
      (node (ref "J2") (pin "2") (pinfunction "2_2") (pintype "passive"))
      (node (ref "J4") (pin "3") (pinfunction "3_3") (pintype "passive"))
      (node (ref "U10") (pin "36") (pinfunction "D-/RG3_36") (pintype "passive"))
    )
    (net (code "9") (name "/FB") (class "Default")
      (node (ref "C3") (pin "1") (pinfunction "1_1") (pintype "passive"))
      (node (ref "R6") (pin "1") (pinfunction "1_1") (pintype "passive"))
      (node (ref "U10") (pin "17") (pinfunction "PGEC1/AN6/RPI38/RB6_17") (pintype "passive"))
    )
    (net (code "10") (name "/GREEN") (class "Default")
      (node (ref "D2") (pin "2") (pinfunction "A_2") (pintype "passive"))
      (node (ref "U10") (pin "47") (pinfunction "PGED2/SOSCI/C3IN3-/RPI61/RC13_47") (pintype "passive"))
    )
    (net (code "11") (name "/LDO3.3V-5.0V") (class "Default")
      (node (ref "R14") (pin "1") (pinfunction "1_1") (pintype "passive"))
      (node (ref "U29") (pin "5") (pinfunction "CTL_5") (pintype "passive"))
      (node (ref "U29") (pin "8") (pinfunction "VCC_8") (pintype "passive"))
      (node (ref "U9") (pin "5") (pinfunction "CTL_5") (pintype "passive"))
      (node (ref "U9") (pin "8") (pinfunction "VCC_8") (pintype "passive"))
    )
    (net (code "12") (name "/LDO5.0V") (class "Default")
      (node (ref "C15") (pin "1") (pinfunction "1_1") (pintype "passive"))
      (node (ref "R11") (pin "1") (pinfunction "1_1") (pintype "passive"))
      (node (ref "R12") (pin "2") (pinfunction "2_2") (pintype "passive"))
      (node (ref "U6") (pin "5") (pinfunction "CTL_5") (pintype "passive"))
      (node (ref "U6") (pin "8") (pinfunction "VCC_8") (pintype "passive"))
    )
    (net (code "13") (name "/LM12V") (class "Default")
      (node (ref "D8") (pin "1") (pinfunction "C_1") (pintype "passive"))
      (node (ref "R13") (pin "1") (pinfunction "1_1") (pintype "passive"))
      (node (ref "U7") (pin "1") (pinfunction "Vin_1") (pintype "passive"))
    )
    (net (code "14") (name "/MCLR") (class "Default")
      (node (ref "C5") (pin "1") (pinfunction "1_1") (pintype "passive"))
      (node (ref "J1") (pin "1") (pinfunction "1_1") (pintype "passive"))
      (node (ref "R1") (pin "1") (pinfunction "1_1") (pintype "passive"))
      (node (ref "U10") (pin "7") (pinfunction "~{MCLR}_7") (pintype "passive"))
    )
    (net (code "15") (name "/MCU5.0V") (class "Default")
      (node (ref "R10") (pin "1") (pinfunction "1_1") (pintype "passive"))
      (node (ref "U10") (pin "34") (pinfunction "VBUS_34") (pintype "passive"))
    )
    (net (code "16") (name "/MEAS12") (class "Default")
      (node (ref "R4") (pin "2") (pinfunction "2_2") (pintype "passive"))
      (node (ref "R5") (pin "2") (pinfunction "2_2") (pintype "passive"))
      (node (ref "U10") (pin "18") (pinfunction "PGED1/AN7/RCV/RPI39/RB7_18") (pintype "passive"))
    )
    (net (code "17") (name "/Main OSC In") (class "Default")
      (node (ref "C10") (pin "1") (pinfunction "1_1") (pintype "passive"))
      (node (ref "U10") (pin "39") (pinfunction "OSC1/RPI60/RC12_39") (pintype "passive"))
      (node (ref "Y1") (pin "1") (pinfunction "1_1") (pintype "passive"))
    )
    (net (code "18") (name "/Main OSC Out") (class "Default")
      (node (ref "C11") (pin "1") (pinfunction "1_1") (pintype "passive"))
      (node (ref "U10") (pin "40") (pinfunction "OSC2/CLKO/RC15_40") (pintype "passive"))
      (node (ref "Y1") (pin "2") (pinfunction "2_2") (pintype "passive"))
    )
    (net (code "19") (name "/ORANGE") (class "Default")
      (node (ref "D4") (pin "2") (pinfunction "A_2") (pintype "passive"))
      (node (ref "U10") (pin "45") (pinfunction "PMCS1/RPI75/RD11_45") (pintype "passive"))
    )
    (net (code "20") (name "/PGC") (class "Default")
      (node (ref "J1") (pin "5") (pinfunction "5_5") (pintype "passive"))
      (node (ref "U10") (pin "15") (pinfunction "PGEC3/AN1/VREF-/RPI33/RB1_15") (pintype "passive"))
    )
    (net (code "21") (name "/PGD") (class "Default")
      (node (ref "J1") (pin "4") (pinfunction "4_4") (pintype "passive"))
      (node (ref "U10") (pin "16") (pinfunction "PGED3/AN0/VREF+/RPI32/RB0_16") (pintype "passive"))
    )
    (net (code "22") (name "/PWM1L") (class "Default")
      (node (ref "U10") (pin "60") (pinfunction "AN24/PWM1L/PMD0/RP80/RE0_60") (pintype "passive"))
    )
    (net (code "23") (name "/PWM2L") (class "Default")
      (node (ref "U10") (pin "62") (pinfunction "AN26/PWM2L/PMD2/RP82/RE2_62") (pintype "passive"))
    )
    (net (code "24") (name "/PWM3H") (class "Default")
      (node (ref "U10") (pin "1") (pinfunction "AN29/PWM3H/PMD5/RP85/RE5_1") (pintype "passive"))
    )
    (net (code "25") (name "/PWM4H") (class "Default")
      (node (ref "U10") (pin "3") (pinfunction "AN31/PWM4H/PMD7/RP87/RE7_3") (pintype "passive"))
    )
    (net (code "26") (name "/RED") (class "Default")
      (node (ref "D1") (pin "2") (pinfunction "A_2") (pintype "passive"))
      (node (ref "U10") (pin "48") (pinfunction "PGEC2/SOSCO/C3IN1-/T1CK/RPI62/RC14_48") (pintype "passive"))
    )
    (net (code "27") (name "/RESET_COLD_L") (class "Default")
      (node (ref "R21") (pin "1") (pinfunction "1_1") (pintype "passive"))
      (node (ref "R29") (pin "1") (pinfunction "1_1") (pintype "passive"))
    )
    (net (code "28") (name "/RESET_pic") (class "Default")
      (node (ref "R21") (pin "2") (pinfunction "2_2") (pintype "passive"))
      (node (ref "U10") (pin "8") (pinfunction "C2IN1-/PMA2/RPI121/RG9_8") (pintype "passive"))
    )
    (net (code "29") (name "/SER_CLK") (class "Default")
      (node (ref "R7") (pin "1") (pinfunction "1_1") (pintype "passive"))
      (node (ref "R8") (pin "1") (pinfunction "1_1") (pintype "passive"))
    )
    (net (code "30") (name "/SER_CLK_pic") (class "Default")
      (node (ref "R7") (pin "2") (pinfunction "2_2") (pintype "passive"))
      (node (ref "U10") (pin "4") (pinfunction "C1IN3-/SCK2/PMA5/RP118/RG6_4") (pintype "passive"))
    )
    (net (code "31") (name "/THDN") (class "Default")
      (node (ref "R9") (pin "1") (pinfunction "1_1") (pintype "passive"))
      (node (ref "U10") (pin "46") (pinfunction "INT0/DMH/RP64/RD0_46") (pintype "passive"))
    )
    (net (code "32") (name "/TXD_0") (class "Default")
      (node (ref "R20") (pin "2") (pinfunction "2_2") (pintype "passive"))
      (node (ref "U10") (pin "6") (pinfunction "C2IN3-/SDO2/PMA3/RP120/RG8_6") (pintype "passive"))
    )
    (net (code "33") (name "/TXD_1") (class "Default")
      (node (ref "R20") (pin "1") (pinfunction "1_1") (pintype "passive"))
      (node (ref "R22") (pin "1") (pinfunction "1_1") (pintype "passive"))
    )
    (net (code "34") (name "/TXD_2") (class "Default")
      (node (ref "Q51") (pin "1") (pinfunction "G_1") (pintype "passive"))
    )
    (net (code "35") (name "/TXD_10") (class "Default")
      (node (ref "Q51") (pin "3") (pinfunction "D_3") (pintype "passive"))
      (node (ref "R18") (pin "2") (pinfunction "2_2") (pintype "passive"))
      (node (ref "U10") (pin "5") (pinfunction "C1IN1-/SDI2/PMA4/RPI119/RG7_5") (pintype "passive"))
    )
    (net (code "36") (name "/USB5.0V") (class "Default")
      (node (ref "D6") (pin "4") (pinfunction "4_4") (pintype "passive"))
      (node (ref "D6") (pin "6") (pinfunction "6_6") (pintype "passive"))
      (node (ref "J2") (pin "1") (pinfunction "1_1") (pintype "passive"))
      (node (ref "J4") (pin "1") (pinfunction "1_1") (pintype "passive"))
      (node (ref "R10") (pin "2") (pinfunction "2_2") (pintype "passive"))
      (node (ref "R11") (pin "2") (pinfunction "2_2") (pintype "passive"))
    )
    (net (code "37") (name "/VCAP") (class "Default")
      (node (ref "C2") (pin "1") (pinfunction "1_1") (pintype "passive"))
      (node (ref "U10") (pin "56") (pinfunction "VCAP_56") (pintype "passive"))
    )
    (net (code "38") (name "/YELLOW") (class "Default")
      (node (ref "D3") (pin "2") (pinfunction "A_2") (pintype "passive"))
      (node (ref "U10") (pin "44") (pinfunction "ASCL1/PMCS2/RPI74/RD10_44") (pintype "passive"))
    )
    (net (code "39") (name "GND") (class "Default")
      (node (ref "C10") (pin "2") (pinfunction "2_2") (pintype "passive"))
      (node (ref "C11") (pin "2") (pinfunction "2_2") (pintype "passive"))
      (node (ref "C12") (pin "2") (pinfunction "2_2") (pintype "passive"))
      (node (ref "C13") (pin "1") (pinfunction "1_1") (pintype "passive"))
      (node (ref "C14") (pin "2") (pinfunction "2_2") (pintype "passive"))
      (node (ref "C15") (pin "2") (pinfunction "2_2") (pintype "passive"))
      (node (ref "C16") (pin "2") (pinfunction "2_2") (pintype "passive"))
      (node (ref "C17") (pin "2") (pinfunction "2_2") (pintype "passive"))
      (node (ref "C2") (pin "2") (pinfunction "2_2") (pintype "passive"))
      (node (ref "C231") (pin "2") (pinfunction "2_2") (pintype "passive"))
      (node (ref "C232") (pin "2") (pinfunction "2_2") (pintype "passive"))
      (node (ref "C3") (pin "2") (pinfunction "2_2") (pintype "passive"))
      (node (ref "C347") (pin "2") (pinfunction "2_2") (pintype "passive"))
      (node (ref "C4") (pin "2") (pinfunction "2_2") (pintype "passive"))
      (node (ref "C5") (pin "2") (pinfunction "2_2") (pintype "passive"))
      (node (ref "C6") (pin "2") (pinfunction "2_2") (pintype "passive"))
      (node (ref "C7") (pin "2") (pinfunction "2_2") (pintype "passive"))
      (node (ref "C8") (pin "2") (pinfunction "2_2") (pintype "passive"))
      (node (ref "C9") (pin "2") (pinfunction "2_2") (pintype "passive"))
      (node (ref "D1") (pin "1") (pinfunction "C_1") (pintype "passive"))
      (node (ref "D2") (pin "1") (pinfunction "C_1") (pintype "passive"))
      (node (ref "D28") (pin "2") (pinfunction "A_2") (pintype "passive"))
      (node (ref "D3") (pin "1") (pinfunction "C_1") (pintype "passive"))
      (node (ref "D4") (pin "1") (pinfunction "C_1") (pintype "passive"))
      (node (ref "D6") (pin "2") (pinfunction "2_2") (pintype "passive"))
      (node (ref "D6") (pin "5") (pinfunction "5_5") (pintype "passive"))
      (node (ref "J1") (pin "3") (pinfunction "3_3") (pintype "passive"))
      (node (ref "J12") (pin "4") (pinfunction "4_4") (pintype "passive"))
      (node (ref "J12") (pin "5") (pinfunction "5_5") (pintype "passive"))
      (node (ref "J12") (pin "6") (pinfunction "6_6") (pintype "passive"))
      (node (ref "J13") (pin "1") (pinfunction "1_1") (pintype "passive"))
      (node (ref "J14") (pin "1") (pinfunction "1_1") (pintype "passive"))
      (node (ref "J15") (pin "1") (pinfunction "1_1") (pintype "passive"))
      (node (ref "J2") (pin "5") (pinfunction "5_5") (pintype "passive"))
      (node (ref "J2") (pin "6") (pinfunction "6_6") (pintype "passive"))
      (node (ref "J2") (pin "7") (pinfunction "7_7") (pintype "passive"))
      (node (ref "J2") (pin "8") (pinfunction "8_8") (pintype "passive"))
      (node (ref "J2") (pin "9") (pinfunction "9_9") (pintype "passive"))
      (node (ref "J22") (pin "1") (pinfunction "1_1") (pintype "passive"))
      (node (ref "J23") (pin "1") (pinfunction "1_1") (pintype "passive"))
      (node (ref "J24") (pin "1") (pinfunction "1_1") (pintype "passive"))
      (node (ref "J3") (pin "2") (pinfunction "2_2") (pintype "passive"))
      (node (ref "J4") (pin "2") (pinfunction "2_2") (pintype "passive"))
      (node (ref "J5") (pin "2") (pinfunction "2_2") (pintype "passive"))
      (node (ref "J5") (pin "3") (pinfunction "3_3") (pintype "passive"))
      (node (ref "J9") (pin "1") (pinfunction "1_1") (pintype "passive"))
      (node (ref "Q51") (pin "2") (pinfunction "S_2") (pintype "passive"))
      (node (ref "R22") (pin "2") (pinfunction "2_2") (pintype "passive"))
      (node (ref "R28") (pin "2") (pinfunction "2_2") (pintype "passive"))
      (node (ref "R29") (pin "2") (pinfunction "2_2") (pintype "passive"))
      (node (ref "R5") (pin "1") (pinfunction "1_1") (pintype "passive"))
      (node (ref "R8") (pin "2") (pinfunction "2_2") (pintype "passive"))
      (node (ref "U10") (pin "20") (pinfunction "AVSS_20") (pintype "passive"))
      (node (ref "U10") (pin "25") (pinfunction "VSS_25") (pintype "passive"))
      (node (ref "U10") (pin "41") (pinfunction "VSS_41") (pintype "passive"))
      (node (ref "U10") (pin "9") (pinfunction "VSS_9") (pintype "passive"))
      (node (ref "U29") (pin "6") (pinfunction "GND_6") (pintype "passive"))
      (node (ref "U29") (pin "7") (pinfunction "GND_7") (pintype "passive"))
      (node (ref "U6") (pin "6") (pinfunction "GND_6") (pintype "passive"))
      (node (ref "U6") (pin "7") (pinfunction "GND_7") (pintype "passive"))
      (node (ref "U7") (pin "4") (pinfunction "GND_4") (pintype "passive"))
      (node (ref "U9") (pin "6") (pinfunction "GND_6") (pintype "passive"))
      (node (ref "U9") (pin "7") (pinfunction "GND_7") (pintype "passive"))
    )
    (net (code "40") (name "Net-(U10-AN2{slash}C2IN2-{slash}VMIO{slash}RPI34{slash}RB2)") (class "Default")
      (node (ref "TP7") (pin "1") (pinfunction "1_1") (pintype "passive"))
      (node (ref "U10") (pin "14") (pinfunction "AN2/C2IN2-/VMIO/RPI34/RB2_14") (pintype "passive"))
    )
    (net (code "41") (name "Net-(U10-AN3{slash}C2IN1+{slash}VPIO{slash}RPI35{slash}RB3)") (class "Default")
      (node (ref "TP6") (pin "1") (pinfunction "1_1") (pintype "passive"))
      (node (ref "U10") (pin "13") (pinfunction "AN3/C2IN1+/VPIO/RPI35/RB3_13") (pintype "passive"))
    )
    (net (code "42") (name "Net-(U10-AN4{slash}C1IN2-{slash}USBOEN{slash}RPI36{slash}RB4)") (class "Default")
      (node (ref "TP5") (pin "1") (pinfunction "1_1") (pintype "passive"))
      (node (ref "U10") (pin "12") (pinfunction "AN4/C1IN2-/USBOEN/RPI36/RB4_12") (pintype "passive"))
    )
    (net (code "43") (name "Net-(U10-AN5{slash}C1IN1+{slash}VBUSON{slash}VBUSST{slash}RPI37{slash}RB5)") (class "Default")
      (node (ref "TP3") (pin "1") (pinfunction "1_1") (pintype "passive"))
      (node (ref "U10") (pin "11") (pinfunction "AN5/C1IN1+/VBUSON/VBUSST/RPI37/RB5_11") (pintype "passive"))
    )
    (net (code "44") (name "Net-(U10-AN8{slash}PMA6{slash}RPI40{slash}RB8)") (class "Default")
      (node (ref "TP10") (pin "1") (pinfunction "1_1") (pintype "passive"))
      (node (ref "U10") (pin "21") (pinfunction "AN8/PMA6/RPI40/RB8_21") (pintype "passive"))
    )
    (net (code "45") (name "Net-(U10-AN9{slash}PMA7{slash}{slash}RPI41{slash}RB9)") (class "Default")
      (node (ref "TP11") (pin "1") (pinfunction "1_1") (pintype "passive"))
      (node (ref "U10") (pin "22") (pinfunction "AN9/PMA7//RPI41/RB9_22") (pintype "passive"))
    )
    (net (code "46") (name "Net-(U10-AN14{slash}PMA1{slash}RPI46{slash}RB14)") (class "Default")
      (node (ref "TP124") (pin "1") (pinfunction "1_1") (pintype "passive"))
      (node (ref "U10") (pin "29") (pinfunction "AN14/PMA1/RPI46/RB14_29") (pintype "passive"))
    )
    (net (code "47") (name "Net-(U10-AN15{slash}PMA0{slash}RPI47{slash}RB15)") (class "Default")
      (node (ref "TP125") (pin "1") (pinfunction "1_1") (pintype "passive"))
      (node (ref "U10") (pin "30") (pinfunction "AN15/PMA0/RPI47/RB15_30") (pintype "passive"))
    )
    (net (code "48") (name "Net-(U10-ASDA1{slash}DPLN{slash}RPI73{slash}RD9)") (class "Default")
      (node (ref "TP12") (pin "1") (pinfunction "1_1") (pintype "passive"))
      (node (ref "U10") (pin "43") (pinfunction "ASDA1/DPLN/RPI73/RD9_43") (pintype "passive"))
    )
    (net (code "49") (name "Net-(U10-C3IN1+{slash}VCMPST3{slash}RP71{slash}RD7)") (class "Default")
      (node (ref "TP18") (pin "1") (pinfunction "1_1") (pintype "passive"))
      (node (ref "U10") (pin "55") (pinfunction "C3IN1+/VCMPST3/RP71/RD7_55") (pintype "passive"))
    )
    (net (code "50") (name "Net-(U10-C3IN2-{slash}RP70{slash}RD6)") (class "Default")
      (node (ref "TP19") (pin "1") (pinfunction "1_1") (pintype "passive"))
      (node (ref "U10") (pin "54") (pinfunction "C3IN2-/RP70/RD6_54") (pintype "passive"))
    )
    (net (code "51") (name "Net-(U10-DPH{slash}RP66{slash}RD2)") (class "Default")
      (node (ref "TP22") (pin "1") (pinfunction "1_1") (pintype "passive"))
      (node (ref "U10") (pin "50") (pinfunction "DPH/RP66/RD2_50") (pintype "passive"))
    )
    (net (code "52") (name "Net-(U10-PMBE{slash}RP67{slash}RD3)") (class "Default")
      (node (ref "TP20") (pin "1") (pinfunction "1_1") (pintype "passive"))
      (node (ref "U10") (pin "51") (pinfunction "PMBE/RP67/RD3_51") (pintype "passive"))
    )
    (net (code "53") (name "Net-(U10-PMRD{slash}RP69{slash}RD5)") (class "Default")
      (node (ref "TP25") (pin "1") (pinfunction "1_1") (pintype "passive"))
      (node (ref "U10") (pin "53") (pinfunction "PMRD/RP69/RD5_53") (pintype "passive"))
    )
    (net (code "54") (name "Net-(U10-RTCC{slash}DMLN{slash}RPI72{slash}RD8)") (class "Default")
      (node (ref "TP13") (pin "1") (pinfunction "1_1") (pintype "passive"))
      (node (ref "U10") (pin "42") (pinfunction "RTCC/DMLN/RPI72/RD8_42") (pintype "passive"))
    )
    (net (code "55") (name "Net-(U10-SCL2{slash}PMA8{slash}RP101{slash}RF5)") (class "Default")
      (node (ref "TP127") (pin "1") (pinfunction "1_1") (pintype "passive"))
      (node (ref "U10") (pin "32") (pinfunction "SCL2/PMA8/RP101/RF5_32") (pintype "passive"))
    )
    (net (code "56") (name "Net-(U10-SDA2{slash}PMA9{slash}RP100{slash}RF4)") (class "Default")
      (node (ref "TP126") (pin "1") (pinfunction "1_1") (pintype "passive"))
      (node (ref "U10") (pin "31") (pinfunction "SDA2/PMA9/RP100/RF4_31") (pintype "passive"))
    )
    (net (code "57") (name "Net-(U10-TCK{slash}AN12{slash}PMA11{slash}RPI44{slash}RB12)") (class "Default")
      (node (ref "TP2") (pin "1") (pinfunction "1_1") (pintype "passive"))
      (node (ref "U10") (pin "27") (pinfunction "TCK/AN12/PMA11/RPI44/RB12_27") (pintype "passive"))
    )
    (net (code "58") (name "Net-(U10-TDI{slash}AN13{slash}PMA10{slash}RPI45{slash}RB13)") (class "Default")
      (node (ref "TP123") (pin "1") (pinfunction "1_1") (pintype "passive"))
      (node (ref "U10") (pin "28") (pinfunction "TDI/AN13/PMA10/RPI45/RB13_28") (pintype "passive"))
    )
    (net (code "59") (name "Net-(U10-TDO{slash}AN11{slash}PMA12{slash}RPI43{slash}RB11)") (class "Default")
      (node (ref "TP132") (pin "1") (pinfunction "1_1") (pintype "passive"))
      (node (ref "U10") (pin "24") (pinfunction "TDO/AN11/PMA12/RPI43/RB11_24") (pintype "passive"))
    )
    (net (code "60") (name "Net-(U10-TMS{slash}AN10{slash}CVREF{slash}PMA13{slash}RPI42{slash}RB10)") (class "Default")
      (node (ref "TP131") (pin "1") (pinfunction "1_1") (pintype "passive"))
      (node (ref "U10") (pin "23") (pinfunction "TMS/AN10/CVREF/PMA13/RPI42/RB10_23") (pintype "passive"))
    )
    (net (code "61") (name "Net-(U10-USBID{slash}RP99{slash}RF3)") (class "Default")
      (node (ref "TP21") (pin "1") (pinfunction "1_1") (pintype "passive"))
      (node (ref "U10") (pin "33") (pinfunction "USBID/RP99/RF3_33") (pintype "passive"))
    )
    (net (code "62") (name "Net-(U10-VCMPST1{slash}RP96{slash}RF0)") (class "Default")
      (node (ref "TP129") (pin "1") (pinfunction "1_1") (pintype "passive"))
      (node (ref "U10") (pin "58") (pinfunction "VCMPST1/RP96/RF0_58") (pintype "passive"))
    )
    (net (code "63") (name "Net-(U10-VCMPST2{slash}RP97{slash}RF1)") (class "Default")
      (node (ref "TP128") (pin "1") (pinfunction "1_1") (pintype "passive"))
      (node (ref "U10") (pin "59") (pinfunction "VCMPST2/RP97/RF1_59") (pintype "passive"))
    )
    (net (code "64") (name "Net-(U10-VCPCON{slash}RP65{slash}RD1)") (class "Default")
      (node (ref "TP23") (pin "1") (pinfunction "1_1") (pintype "passive"))
      (node (ref "U10") (pin "49") (pinfunction "VCPCON/RP65/RD1_49") (pintype "passive"))
    )
    (net (code "65") (name "Net-(U29-ADJ)") (class "Default")
      (node (ref "R27") (pin "2") (pinfunction "2_2") (pintype "passive"))
      (node (ref "R28") (pin "1") (pinfunction "1_1") (pintype "passive"))
      (node (ref "U29") (pin "2") (pinfunction "ADJ_2") (pintype "passive"))
    )
    (net (code "66") (name "unconnected-(J2-Pad4)") (class "Default")
      (node (ref "J2") (pin "4") (pinfunction "4_4") (pintype "passive+no_connect"))
    )
    (net (code "67") (name "unconnected-(U6-NC-Pad2)") (class "Default")
      (node (ref "U6") (pin "2") (pinfunction "NC_2") (pintype "passive+no_connect"))
    )
    (net (code "68") (name "unconnected-(U6-NC-Pad3)") (class "Default")
      (node (ref "U6") (pin "3") (pinfunction "NC_3") (pintype "passive+no_connect"))
    )
    (net (code "69") (name "unconnected-(U6-NC-Pad4)") (class "Default")
      (node (ref "U6") (pin "4") (pinfunction "NC_4") (pintype "passive+no_connect"))
    )
    (net (code "70") (name "unconnected-(U9-ADJ-Pad2)") (class "Default")
      (node (ref "U9") (pin "2") (pinfunction "ADJ_2") (pintype "passive+no_connect"))
    )
    (net (code "71") (name "unconnected-(U9-NC-Pad3)") (class "Default")
      (node (ref "U9") (pin "3") (pinfunction "NC_3") (pintype "passive+no_connect"))
    )
    (net (code "72") (name "unconnected-(U9-NC-Pad4)") (class "Default")
      (node (ref "U9") (pin "4") (pinfunction "NC_4") (pintype "passive+no_connect"))
    )
    (net (code "73") (name "unconnected-(U10-AN25{slash}PWM1H{slash}PMD1{slash}RPI81{slash}RE1-Pad61)") (class "Default")
      (node (ref "U10") (pin "61") (pinfunction "AN25/PWM1H/PMD1/RPI81/RE1_61") (pintype "passive+no_connect"))
    )
    (net (code "74") (name "unconnected-(U10-AN27{slash}PWM2H{slash}PMD3{slash}RPI83{slash}RE3-Pad63)") (class "Default")
      (node (ref "U10") (pin "63") (pinfunction "AN27/PWM2H/PMD3/RPI83/RE3_63") (pintype "passive+no_connect"))
    )
    (net (code "75") (name "unconnected-(U10-AN28{slash}PWM3L{slash}PMD4{slash}RP84{slash}RE4-Pad64)") (class "Default")
      (node (ref "U10") (pin "64") (pinfunction "AN28/PWM3L/PMD4/RP84/RE4_64") (pintype "passive+no_connect"))
    )
    (net (code "76") (name "unconnected-(U10-AN30{slash}PWM4L{slash}PMD6{slash}RPI86{slash}RE6-Pad2)") (class "Default")
      (node (ref "U10") (pin "2") (pinfunction "AN30/PWM4L/PMD6/RPI86/RE6_2") (pintype "passive+no_connect"))
    )
    (net (code "77") (name "unconnected-(U10-PMWR{slash}RP68{slash}RD4-Pad52)") (class "Default")
      (node (ref "U10") (pin "52") (pinfunction "PMWR/RP68/RD4_52") (pintype "passive+no_connect"))
    )
    (net (code "78") (name "unconnected-(U29-NC-Pad3)") (class "Default")
      (node (ref "U29") (pin "3") (pinfunction "NC_3") (pintype "passive+no_connect"))
    )
    (net (code "79") (name "unconnected-(U29-NC-Pad4)") (class "Default")
      (node (ref "U29") (pin "4") (pinfunction "NC_4") (pintype "passive+no_connect"))
    )
  )
)
